# Analog_Input_Conditioning.net
KiCad netlist of a schematic drawn in Altium Designer
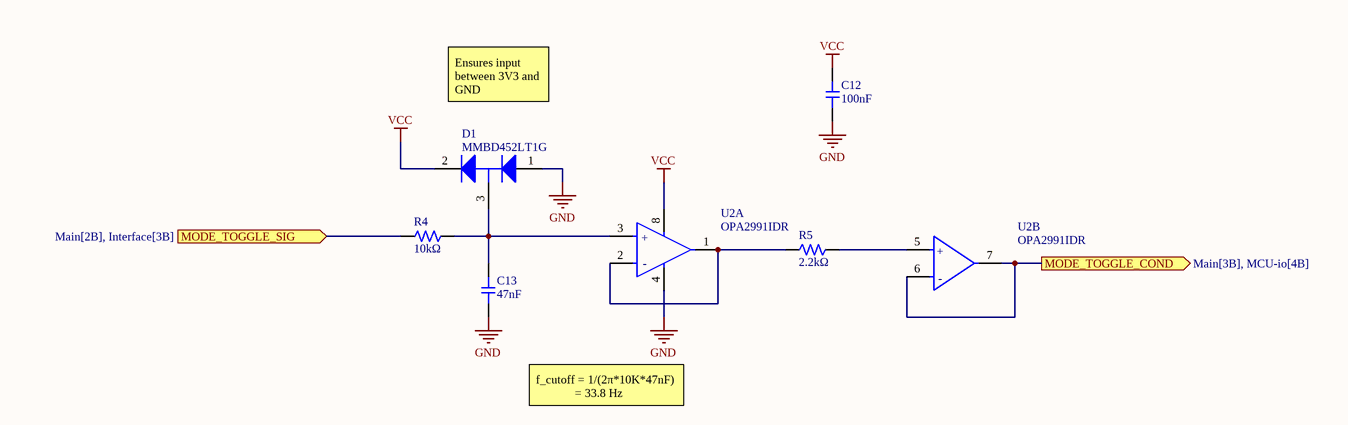
[diagram p0: Analog Input Conditioning.SchDoc]

(export (version "E")
  (design (tool "Eeschema 10.0.6"))
  (components
    (comp (ref "C12")
      (value "CC0603KRX7R9BB104")
      (footprint "CAP-0603")
      (description "Capacitor, Ceramic (MLCC), 100nF, ±10%, 50V, X7R, ±10%, SMD 0603")
      (fields
        (field (name "JLCPCB BASIC PART") "Yes")
        (field (name "CAPACITANCE") "100nF")
        (field (name "JLCPCB PART NUMBER") "C14663")
      )
      (libsource (lib "JLCCapacitor") (part "CC0603KRX7R9BB104"))
    )
    (comp (ref "C13")
      (value "CL10B473KB8NNNC")
      (footprint "CAP-0603")
      (description "Capacitor, Ceramic (MLCC), 47nF, ±10%, 50V, X7R, ±10%, SMD 0603")
      (fields
        (field (name "JLCPCB BASIC PART") "Yes")
        (field (name "CAPACITANCE") "47nF")
        (field (name "JLCPCB PART NUMBER") "C1622")
      )
      (libsource (lib "JLCCapacitor") (part "CL10B473KB8NNNC"))
    )
    (comp (ref "D1")
      (value "MMBD452LT1G")
      (footprint "ONSC-SOT-23-3-318-08_V")
      (description "30V SCHOTTKY")
      (fields
        (field (name "MANUFACTURER") "On Semiconductor")
        (field (name "MANUFACTURER_1") "ON Semiconductor")
      )
      (libsource (lib "DiodesAndFuses") (part "MMBD452LT1G"))
    )
    (comp (ref "R4")
      (value "0603WAF1002T5E")
      (footprint "RES-0603")
      (description "Resistor, 10kΩ, ±1%, 100mW, 75V, ±100ppm/℃, -55℃~+155℃, SMD 0603")
      (fields
        (field (name "MANUFACTURER") "Uniroyal")
        (field (name "JLCPCB PART NUMBER") "C25804")
        (field (name "RESISTANCE") "10kΩ")
      )
      (libsource (lib "JLCResistor") (part "0603WAF1002T5E"))
    )
    (comp (ref "R5")
      (value "0603WAF2201T5E")
      (footprint "RES-0603")
      (description "Resistor, 2.2kΩ, ±1%, 100mW, 75V, ±100ppm/℃, -55℃~+155℃, SMD 0603")
      (fields
        (field (name "MANUFACTURER") "Uniroyal")
        (field (name "JLCPCB PART NUMBER") "C4190")
        (field (name "RESISTANCE") "2.2kΩ")
      )
      (libsource (lib "JLCResistor") (part "0603WAF2201T5E"))
    )
    (comp (ref "U2")
      (value "OPA2991IDR")
      (footprint "FP-D0008A-IPC_C")
      (description "IC OPAMP GP 2 CIRCUIT 8SOIC")
      (fields (field (name "MANUFACTURER") "Texas Instruments"))
      (libsource (lib "LogicAndOpAmps") (part "OPA2991IDR"))
    )
  )
  (nets
    (net (code "1") (name "/MODE_TOGGLE_COND") (class "Default")
      (node (ref "U2") (pin "6") (pinfunction "IN2-_6") (pintype "tri_state"))
      (node (ref "U2") (pin "7") (pinfunction "OUT2_7") (pintype "passive"))
    )
    (net (code "2") (name "/MODE_TOGGLE_SIG") (class "Default")
      (node (ref "R4") (pin "1") (pinfunction "1_1") (pintype "passive"))
    )
    (net (code "3") (name "GND") (class "Default")
      (node (ref "C12") (pin "1") (pinfunction "1_1") (pintype "passive"))
      (node (ref "C13") (pin "1") (pinfunction "1_1") (pintype "passive"))
      (node (ref "D1") (pin "1") (pinfunction "A_1") (pintype "passive"))
      (node (ref "U2") (pin "4") (pinfunction "V-_4") (pintype "power_in"))
    )
    (net (code "4") (name "Net-(D1-K{slash}A)") (class "Default")
      (node (ref "C13") (pin "2") (pinfunction "2_2") (pintype "passive"))
      (node (ref "D1") (pin "3") (pinfunction "K/A_3") (pintype "passive"))
      (node (ref "R4") (pin "2") (pinfunction "2_2") (pintype "passive"))
      (node (ref "U2") (pin "3") (pinfunction "IN1+_3") (pintype "tri_state"))
    )
    (net (code "5") (name "Net-(U2A-IN1-)") (class "Default")
      (node (ref "R5") (pin "1") (pinfunction "1_1") (pintype "passive"))
      (node (ref "U2") (pin "1") (pinfunction "OUT1_1") (pintype "passive"))
      (node (ref "U2") (pin "2") (pinfunction "IN1-_2") (pintype "tri_state"))
    )
    (net (code "6") (name "Net-(U2B-IN2+)") (class "Default")
      (node (ref "R5") (pin "2") (pinfunction "2_2") (pintype "passive"))
      (node (ref "U2") (pin "5") (pinfunction "IN2+_5") (pintype "tri_state"))
    )
    (net (code "7") (name "VCC") (class "Default")
      (node (ref "C12") (pin "2") (pinfunction "2_2") (pintype "passive"))
      (node (ref "D1") (pin "2") (pinfunction "K_2") (pintype "passive"))
      (node (ref "U2") (pin "8") (pinfunction "V+_8") (pintype "power_in"))
    )
  )
)
